# MicroSwitch.net
KiCad netlist of a schematic drawn in Altium Designer
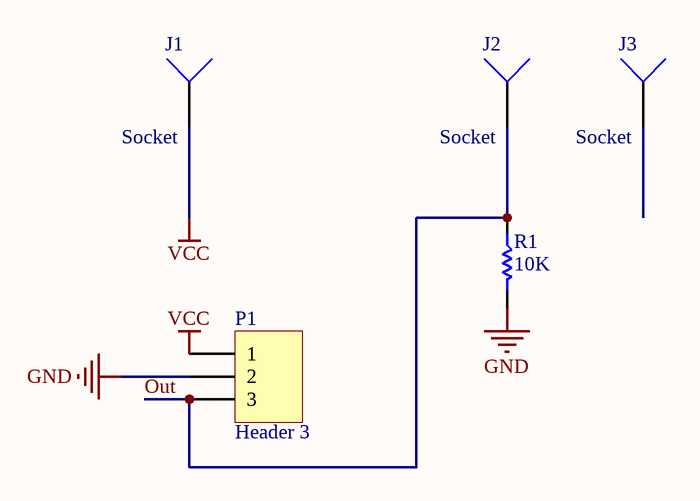
[diagram p0: MicroSwitch.SchDoc]

(export (version "E")
  (design (tool "Eeschema 10.0.6"))
  (components
    (comp (ref "J1")
      (value "Socket")
      (footprint "PIN1")
      (fields (field (name "PUBLISHER") "Altium Limited"))
      (libsource (lib "Miscellaneous Connectors") (part "Socket"))
    )
    (comp (ref "J2")
      (value "Socket")
      (footprint "PIN1")
      (fields (field (name "PUBLISHER") "Altium Limited"))
      (libsource (lib "Miscellaneous Connectors") (part "Socket"))
    )
    (comp (ref "J3")
      (value "Socket")
      (footprint "PIN1")
      (fields (field (name "PUBLISHER") "Altium Limited"))
      (libsource (lib "Miscellaneous Connectors") (part "Socket"))
    )
    (comp (ref "P1")
      (value "Header 3")
      (footprint "HDR1X3")
      (description "Header, 3-Pin")
      (fields (field (name "PUBLISHER") "Altium Limited"))
      (libsource (lib "Miscellaneous Connectors") (part "Header 3"))
    )
    (comp (ref "R1") (value "10K") (footprint "6-0805_L") (libsource (lib "3D LIB") (part "RESISTOR")))
  )
  (nets
    (net (code "1") (name "/Out") (class "Default")
      (node (ref "J2") (pin "1") (pinfunction "1_1") (pintype "passive"))
      (node (ref "P1") (pin "3") (pinfunction "3_3") (pintype "passive"))
      (node (ref "R1") (pin "1") (pinfunction "1_1") (pintype "passive"))
    )
    (net (code "2") (name "GND") (class "Default")
      (node (ref "P1") (pin "2") (pinfunction "2_2") (pintype "passive"))
      (node (ref "R1") (pin "2") (pinfunction "2_2") (pintype "passive"))
    )
    (net (code "3") (name "VCC") (class "Default")
      (node (ref "J1") (pin "1") (pinfunction "1_1") (pintype "passive"))
      (node (ref "P1") (pin "1") (pinfunction "1_1") (pintype "passive"))
    )
    (net (code "4") (name "unconnected-(J3-Pad1)") (class "Default")
      (node (ref "J3") (pin "1") (pinfunction "1_1") (pintype "passive"))
    )
  )
)
